# Mach_PCB.net
KiCad netlist of a schematic drawn in Altium Designer
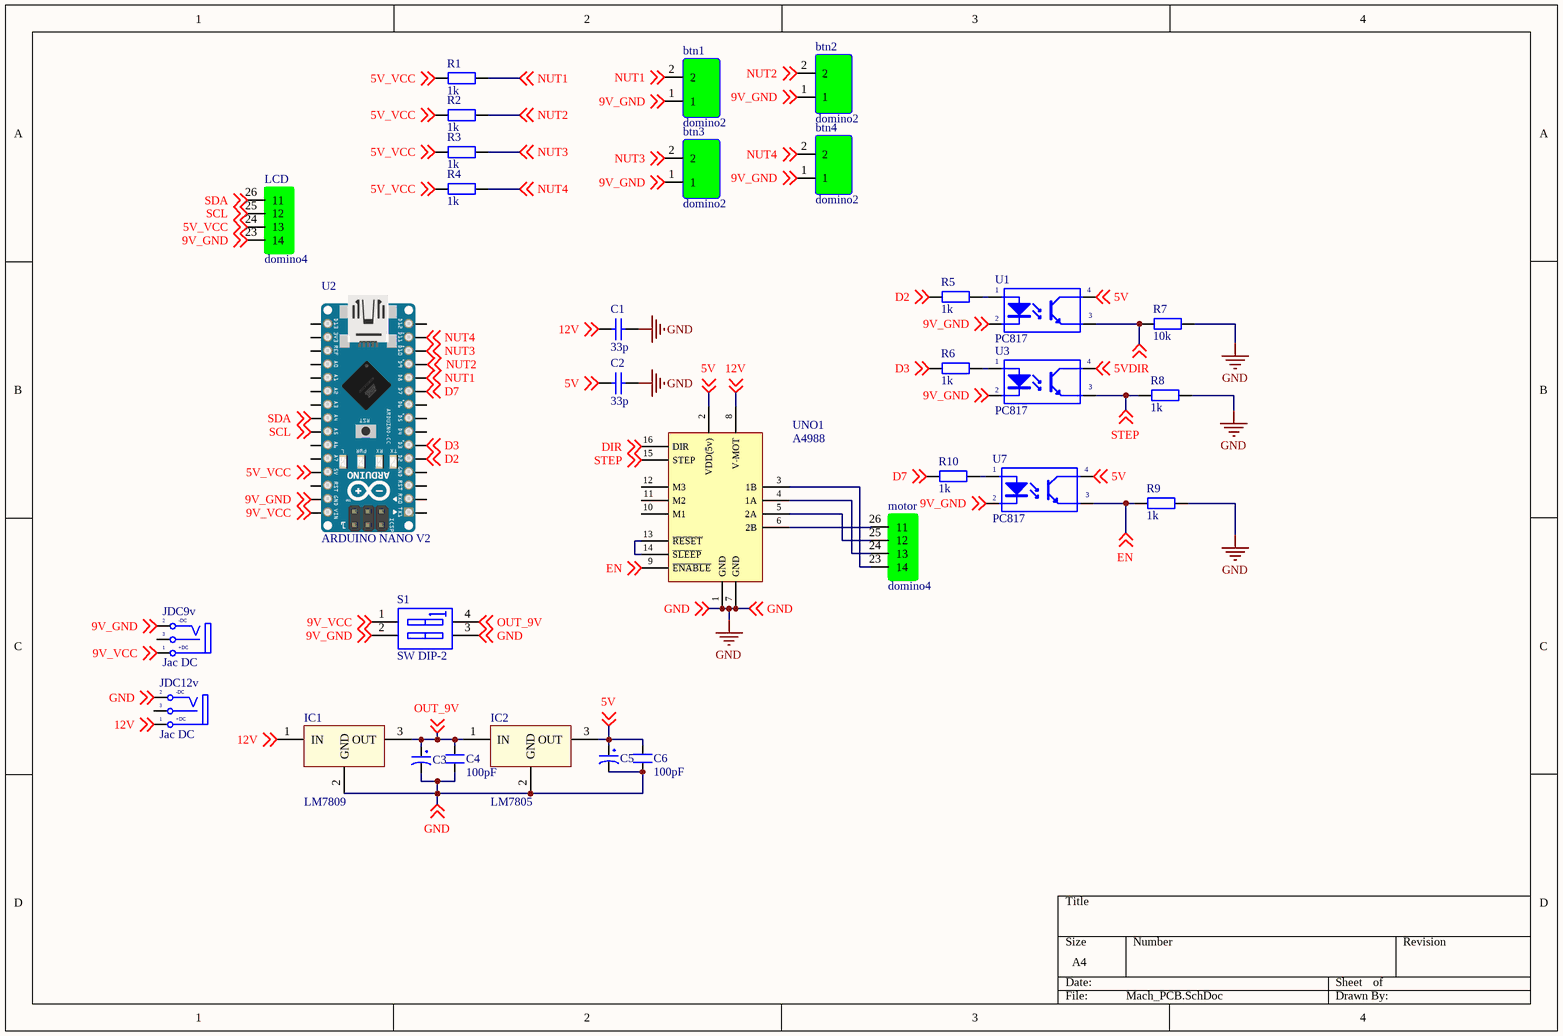
[diagram p0: Mach_PCB.SchDoc]

(export (version "E")
  (design (tool "Eeschema 10.0.6"))
  (components
    (comp (ref "btn1")
      (value "domino2")
      (footprint "domino2")
      (libsource (lib "Nanjar's Library") (part "domino2"))
    )
    (comp (ref "btn2")
      (value "domino2")
      (footprint "domino2")
      (libsource (lib "Nanjar's Library") (part "domino2"))
    )
    (comp (ref "btn3")
      (value "domino2")
      (footprint "domino2")
      (libsource (lib "Nanjar's Library") (part "domino2"))
    )
    (comp (ref "btn4")
      (value "domino2")
      (footprint "domino2")
      (libsource (lib "Nanjar's Library") (part "domino2"))
    )
    (comp (ref "C1")
      (value "33p")
      (footprint "Tu-ceramic")
      (description "Capacitor")
      (fields (field (name "Comment") "Capacitor Ceramic") (field (name "PUBLISHER") "Altium Limited"))
      (libsource (lib "NBBLib 14-03-2012") (part "CapDecop"))
    )
    (comp (ref "C2")
      (value "33p")
      (footprint "Tu-ceramic")
      (description "Capacitor")
      (fields (field (name "Comment") "Capacitor Ceramic") (field (name "PUBLISHER") "Altium Limited"))
      (libsource (lib "NBBLib 14-03-2012") (part "CapDecop"))
    )
    (comp (ref "C3")
      (value "100uF/35V")
      (footprint "CP1.5/3.4")
      (description "Cap 100uF/35V - 470uF/16V")
      (libsource (lib "Cty1") (part "CP3"))
    )
    (comp (ref "C4")
      (value "100pF")
      (footprint "CN1")
      (description "Cap np  1pF - 472pF")
      (libsource (lib "Cty1") (part "CN1"))
    )
    (comp (ref "C5")
      (value "100uF/35V")
      (footprint "CP1.5/3.4")
      (description "Cap 100uF/35V - 470uF/16V")
      (libsource (lib "Cty1") (part "CP3"))
    )
    (comp (ref "C6")
      (value "100pF")
      (footprint "CN1")
      (description "Cap np  1pF - 472pF")
      (libsource (lib "Cty1") (part "CN1"))
    )
    (comp (ref "IC1")
      (value "LM7809")
      (footprint "QTO-220")
      (description "On ap +, from + 5 to + 24VDC")
      (libsource (lib "Cty1") (part "LM78xx"))
    )
    (comp (ref "IC2")
      (value "LM7805")
      (footprint "QTO-220")
      (description "On ap +, from + 5 to + 24VDC")
      (libsource (lib "Cty1") (part "LM78xx"))
    )
    (comp (ref "JDC9v")
      (value "Jac DC")
      (footprint "DC-IN")
      (description "Jac DC input")
      (libsource (lib "Cty1") (part "DCIN"))
    )
    (comp (ref "JDC12v")
      (value "Jac DC")
      (footprint "DC-IN")
      (description "Jac DC input")
      (libsource (lib "Cty1") (part "DCIN"))
    )
    (comp (ref "LCD")
      (value "domino4")
      (footprint "domino4")
      (libsource (lib "Nanjar's Library") (part "domino4"))
    )
    (comp (ref "motor")
      (value "domino4")
      (footprint "domino4")
      (libsource (lib "Nanjar's Library") (part "domino4"))
    )
    (comp (ref "R1")
      (value "1k")
      (footprint "R1/4W")
      (description "Resistor 1/4W")
      (libsource (lib "Cty1") (part "R1/4W"))
    )
    (comp (ref "R2")
      (value "1k")
      (footprint "R1/4W")
      (description "Resistor 1/4W")
      (libsource (lib "Cty1") (part "R1/4W"))
    )
    (comp (ref "R3")
      (value "1k")
      (footprint "R1/4W")
      (description "Resistor 1/4W")
      (libsource (lib "Cty1") (part "R1/4W"))
    )
    (comp (ref "R4")
      (value "1k")
      (footprint "R1/4W")
      (description "Resistor 1/4W")
      (libsource (lib "Cty1") (part "R1/4W"))
    )
    (comp (ref "R5")
      (value "1k")
      (footprint "R1/4W")
      (description "Resistor 1/4W")
      (libsource (lib "Cty1") (part "R1/4W"))
    )
    (comp (ref "R6")
      (value "1k")
      (footprint "R1/4W")
      (description "Resistor 1/4W")
      (libsource (lib "Cty1") (part "R1/4W"))
    )
    (comp (ref "R7")
      (value "10k")
      (footprint "R1/4W")
      (description "Resistor 1/4W")
      (libsource (lib "Cty1") (part "R1/4W"))
    )
    (comp (ref "R8")
      (value "1k")
      (footprint "R1/4W")
      (description "Resistor 1/4W")
      (libsource (lib "Cty1") (part "R1/4W"))
    )
    (comp (ref "R9")
      (value "1k")
      (footprint "R1/4W")
      (description "Resistor 1/4W")
      (libsource (lib "Cty1") (part "R1/4W"))
    )
    (comp (ref "R10")
      (value "1k")
      (footprint "R1/4W")
      (description "Resistor 1/4W")
      (libsource (lib "Cty1") (part "R1/4W"))
    )
    (comp (ref "S1")
      (value "SW DIP-2")
      (footprint "DIP2")
      (description "DIP Switch, 2 Position, SPST")
      (fields (field (name "PUBLISHER") "Altium Limited"))
      (libsource (lib "My Library") (part "SW DIP-2"))
    )
    (comp (ref "U1")
      (value "PC817")
      (footprint "DIP4/W0.3")
      (description "Single Opto")
      (libsource (lib "syhaunguyen") (part "PC817"))
    )
    (comp (ref "U2")
      (value "ARDUINO NANO V2")
      (footprint "ARDUINO NANO")
      (libsource (lib "Nanjar's Library") (part "ARDUINO NANO V2"))
    )
    (comp (ref "U3")
      (value "PC817")
      (footprint "DIP4/W0.3")
      (description "Single Opto")
      (libsource (lib "syhaunguyen") (part "PC817"))
    )
    (comp (ref "U7")
      (value "PC817")
      (footprint "DIP4/W0.3")
      (description "Single Opto")
      (libsource (lib "syhaunguyen") (part "PC817"))
    )
    (comp (ref "UNO1")
      (value "A4988")
      (footprint "A4988(driver)")
      (libsource (lib "My Library") (part "A4988"))
    )
  )
  (nets
    (net (code "1") (name "5V") (class "Default")
      (node (ref "C2") (pin "2") (pinfunction "2_2") (pintype "passive"))
      (node (ref "C5") (pin "1") (pinfunction "1_1") (pintype "passive"))
      (node (ref "C6") (pin "1") (pinfunction "1_1") (pintype "passive"))
      (node (ref "IC2") (pin "3") (pinfunction "OUT_3") (pintype "passive"))
      (node (ref "U1") (pin "4") (pinfunction "C_4") (pintype "passive"))
      (node (ref "U3") (pin "4") (pinfunction "C_4") (pintype "passive"))
      (node (ref "U7") (pin "4") (pinfunction "C_4") (pintype "passive"))
      (node (ref "UNO1") (pin "2") (pinfunction "VDD(5v)_2") (pintype "power_in"))
    )
    (net (code "2") (name "5V_VCC") (class "Default")
      (node (ref "LCD") (pin "24") (pinfunction "13_24") (pintype "passive"))
      (node (ref "R1") (pin "1") (pinfunction "1_1") (pintype "passive"))
      (node (ref "R2") (pin "1") (pinfunction "1_1") (pintype "passive"))
      (node (ref "R3") (pin "1") (pinfunction "1_1") (pintype "passive"))
      (node (ref "R4") (pin "1") (pinfunction "1_1") (pintype "passive"))
      (node (ref "U2") (pin "27") (pinfunction "5V_27") (pintype "passive"))
    )
    (net (code "3") (name "9V_GND") (class "Default")
      (node (ref "JDC9v") (pin "2") (pinfunction "TN_2") (pintype "passive"))
      (node (ref "LCD") (pin "23") (pinfunction "14_23") (pintype "passive"))
      (node (ref "S1") (pin "2") (pinfunction "A2_2") (pintype "passive"))
      (node (ref "U1") (pin "2") (pinfunction "K_2") (pintype "passive"))
      (node (ref "U2") (pin "29") (pinfunction "GND_29") (pintype "passive"))
      (node (ref "U3") (pin "2") (pinfunction "K_2") (pintype "passive"))
      (node (ref "U7") (pin "2") (pinfunction "K_2") (pintype "passive"))
      (node (ref "btn1") (pin "1") (pinfunction "1_1") (pintype "passive"))
      (node (ref "btn2") (pin "1") (pinfunction "1_1") (pintype "passive"))
      (node (ref "btn3") (pin "1") (pinfunction "1_1") (pintype "passive"))
      (node (ref "btn4") (pin "1") (pinfunction "1_1") (pintype "passive"))
    )
    (net (code "4") (name "9V_VCC") (class "Default")
      (node (ref "JDC9v") (pin "1") (pinfunction "T_1") (pintype "passive"))
      (node (ref "S1") (pin "1") (pinfunction "A1_1") (pintype "passive"))
      (node (ref "U2") (pin "30") (pinfunction "VIN_30") (pintype "passive"))
    )
    (net (code "5") (name "12V") (class "Default")
      (node (ref "C1") (pin "2") (pinfunction "2_2") (pintype "passive"))
      (node (ref "IC1") (pin "1") (pinfunction "IN_1") (pintype "passive"))
      (node (ref "JDC12v") (pin "1") (pinfunction "T_1") (pintype "passive"))
      (node (ref "UNO1") (pin "8") (pinfunction "V-MOT_8") (pintype "power_in"))
    )
    (net (code "6") (name "D2") (class "Default")
      (node (ref "R5") (pin "1") (pinfunction "1_1") (pintype "passive"))
      (node (ref "U2") (pin "5") (pinfunction "D2_5") (pintype "passive"))
    )
    (net (code "7") (name "D3") (class "Default")
      (node (ref "R6") (pin "1") (pinfunction "1_1") (pintype "passive"))
      (node (ref "U2") (pin "6") (pinfunction "D3_6") (pintype "passive"))
    )
    (net (code "8") (name "D7") (class "Default")
      (node (ref "R10") (pin "1") (pinfunction "1_1") (pintype "passive"))
      (node (ref "U2") (pin "10") (pinfunction "D7_10") (pintype "passive"))
    )
    (net (code "9") (name "DIR") (class "Default")
      (node (ref "R7") (pin "1") (pinfunction "1_1") (pintype "passive"))
      (node (ref "U1") (pin "3") (pinfunction "E_3") (pintype "passive"))
      (node (ref "UNO1") (pin "16") (pinfunction "DIR_16") (pintype "power_in"))
    )
    (net (code "10") (name "EN") (class "Default")
      (node (ref "R9") (pin "1") (pinfunction "1_1") (pintype "passive"))
      (node (ref "U7") (pin "3") (pinfunction "E_3") (pintype "passive"))
      (node (ref "UNO1") (pin "9") (pinfunction "~{ENABLE}_9") (pintype "power_in"))
    )
    (net (code "11") (name "GND") (class "Default")
      (node (ref "C1") (pin "1") (pinfunction "1_1") (pintype "passive"))
      (node (ref "C2") (pin "1") (pinfunction "1_1") (pintype "passive"))
      (node (ref "C3") (pin "2") (pinfunction "2_2") (pintype "passive"))
      (node (ref "C4") (pin "2") (pinfunction "2_2") (pintype "passive"))
      (node (ref "C5") (pin "2") (pinfunction "2_2") (pintype "passive"))
      (node (ref "C6") (pin "2") (pinfunction "2_2") (pintype "passive"))
      (node (ref "IC1") (pin "2") (pinfunction "GND_2") (pintype "passive"))
      (node (ref "IC2") (pin "2") (pinfunction "GND_2") (pintype "passive"))
      (node (ref "JDC12v") (pin "2") (pinfunction "TN_2") (pintype "passive"))
      (node (ref "R7") (pin "2") (pinfunction "2_2") (pintype "passive"))
      (node (ref "R8") (pin "2") (pinfunction "2_2") (pintype "passive"))
      (node (ref "R9") (pin "2") (pinfunction "2_2") (pintype "passive"))
      (node (ref "S1") (pin "3") (pinfunction "B2_3") (pintype "passive"))
      (node (ref "UNO1") (pin "1") (pinfunction "GND_1") (pintype "power_in"))
      (node (ref "UNO1") (pin "7") (pinfunction "GND_7") (pintype "power_in"))
    )
    (net (code "12") (name "NUT1") (class "Default")
      (node (ref "R1") (pin "2") (pinfunction "2_2") (pintype "passive"))
      (node (ref "U2") (pin "11") (pinfunction "D8_11") (pintype "passive"))
      (node (ref "btn1") (pin "2") (pinfunction "2_2") (pintype "passive"))
    )
    (net (code "13") (name "NUT2") (class "Default")
      (node (ref "R2") (pin "2") (pinfunction "2_2") (pintype "passive"))
      (node (ref "btn2") (pin "2") (pinfunction "2_2") (pintype "passive"))
    )
    (net (code "14") (name "NUT3") (class "Default")
      (node (ref "R3") (pin "2") (pinfunction "2_2") (pintype "passive"))
      (node (ref "U2") (pin "13") (pinfunction "D10_13") (pintype "passive"))
      (node (ref "btn3") (pin "2") (pinfunction "2_2") (pintype "passive"))
    )
    (net (code "15") (name "NUT4") (class "Default")
      (node (ref "R4") (pin "2") (pinfunction "2_2") (pintype "passive"))
      (node (ref "U2") (pin "14") (pinfunction "D11_14") (pintype "passive"))
      (node (ref "btn4") (pin "2") (pinfunction "2_2") (pintype "passive"))
    )
    (net (code "16") (name "Net-(U1-A)") (class "Default")
      (node (ref "R5") (pin "2") (pinfunction "2_2") (pintype "passive"))
      (node (ref "U1") (pin "1") (pinfunction "A_1") (pintype "passive"))
    )
    (net (code "17") (name "Net-(U3-A)") (class "Default")
      (node (ref "R6") (pin "2") (pinfunction "2_2") (pintype "passive"))
      (node (ref "U3") (pin "1") (pinfunction "A_1") (pintype "passive"))
    )
    (net (code "18") (name "Net-(U7-A)") (class "Default")
      (node (ref "R10") (pin "2") (pinfunction "2_2") (pintype "passive"))
      (node (ref "U7") (pin "1") (pinfunction "A_1") (pintype "passive"))
    )
    (net (code "19") (name "Net-(UNO1-1A)") (class "Default")
      (node (ref "UNO1") (pin "4") (pinfunction "1A_4") (pintype "power_in"))
      (node (ref "motor") (pin "24") (pinfunction "13_24") (pintype "passive"))
    )
    (net (code "20") (name "Net-(UNO1-1B)") (class "Default")
      (node (ref "UNO1") (pin "3") (pinfunction "1B_3") (pintype "power_in"))
      (node (ref "motor") (pin "23") (pinfunction "14_23") (pintype "passive"))
    )
    (net (code "21") (name "Net-(UNO1-2A)") (class "Default")
      (node (ref "UNO1") (pin "5") (pinfunction "2A_5") (pintype "power_in"))
      (node (ref "motor") (pin "25") (pinfunction "12_25") (pintype "passive"))
    )
    (net (code "22") (name "Net-(UNO1-2B)") (class "Default")
      (node (ref "UNO1") (pin "6") (pinfunction "2B_6") (pintype "power_in"))
      (node (ref "motor") (pin "26") (pinfunction "11_26") (pintype "passive"))
    )
    (net (code "23") (name "Net-(UNO1-~{RESET})") (class "Default")
      (node (ref "UNO1") (pin "13") (pinfunction "~{RESET}_13") (pintype "power_in"))
      (node (ref "UNO1") (pin "14") (pinfunction "~{SLEEP}_14") (pintype "power_in"))
    )
    (net (code "24") (name "OUT_9V") (class "Default")
      (node (ref "C3") (pin "1") (pinfunction "1_1") (pintype "passive"))
      (node (ref "C4") (pin "1") (pinfunction "1_1") (pintype "passive"))
      (node (ref "IC1") (pin "3") (pinfunction "OUT_3") (pintype "passive"))
      (node (ref "IC2") (pin "1") (pinfunction "IN_1") (pintype "passive"))
      (node (ref "S1") (pin "4") (pinfunction "B1_4") (pintype "passive"))
    )
    (net (code "25") (name "SCL") (class "Default")
      (node (ref "LCD") (pin "25") (pinfunction "12_25") (pintype "passive"))
      (node (ref "U2") (pin "24") (pinfunction "A5_24") (pintype "passive"))
    )
    (net (code "26") (name "SDA") (class "Default")
      (node (ref "LCD") (pin "26") (pinfunction "11_26") (pintype "passive"))
      (node (ref "U2") (pin "23") (pinfunction "A4_23") (pintype "passive"))
    )
    (net (code "27") (name "STEP") (class "Default")
      (node (ref "R8") (pin "1") (pinfunction "1_1") (pintype "passive"))
      (node (ref "U3") (pin "3") (pinfunction "E_3") (pintype "passive"))
      (node (ref "UNO1") (pin "15") (pinfunction "STEP_15") (pintype "power_in"))
    )
    (net (code "28") (name "unconnected-(JDC9v-S-Pad3)") (class "Default")
      (node (ref "JDC9v") (pin "3") (pinfunction "S_3") (pintype "power_in"))
    )
    (net (code "29") (name "unconnected-(JDC12v-S-Pad3)") (class "Default")
      (node (ref "JDC12v") (pin "3") (pinfunction "S_3") (pintype "power_in"))
    )
    (net (code "30") (name "unconnected-(U2-3-PadRST)") (class "Default")
      (node (ref "U2") (pin "RST") (pinfunction "3_RST") (pintype "passive"))
    )
    (net (code "31") (name "unconnected-(U2-3V3-Pad17)") (class "Default")
      (node (ref "U2") (pin "17") (pinfunction "3V3_17") (pintype "passive"))
    )
    (net (code "32") (name "unconnected-(U2-A0-Pad19)") (class "Default")
      (node (ref "U2") (pin "19") (pinfunction "A0_19") (pintype "passive"))
    )
    (net (code "33") (name "unconnected-(U2-A1-Pad20)") (class "Default")
      (node (ref "U2") (pin "20") (pinfunction "A1_20") (pintype "passive"))
    )
    (net (code "34") (name "unconnected-(U2-A2-Pad21)") (class "Default")
      (node (ref "U2") (pin "21") (pinfunction "A2_21") (pintype "passive"))
    )
    (net (code "35") (name "unconnected-(U2-A3-Pad22)") (class "Default")
      (node (ref "U2") (pin "22") (pinfunction "A3_22") (pintype "passive"))
    )
    (net (code "36") (name "unconnected-(U2-A6-Pad25)") (class "Default")
      (node (ref "U2") (pin "25") (pinfunction "A6_25") (pintype "passive"))
    )
    (net (code "37") (name "unconnected-(U2-A7-Pad26)") (class "Default")
      (node (ref "U2") (pin "26") (pinfunction "A7_26") (pintype "passive"))
    )
    (net (code "38") (name "unconnected-(U2-AREF-Pad18)") (class "Default")
      (node (ref "U2") (pin "18") (pinfunction "AREF_18") (pintype "passive"))
    )
    (net (code "39") (name "unconnected-(U2-D4-Pad7)") (class "Default")
      (node (ref "U2") (pin "7") (pinfunction "D4_7") (pintype "passive"))
    )
    (net (code "40") (name "unconnected-(U2-D5-Pad8)") (class "Default")
      (node (ref "U2") (pin "8") (pinfunction "D5_8") (pintype "passive"))
    )
    (net (code "41") (name "unconnected-(U2-D6-Pad9)") (class "Default")
      (node (ref "U2") (pin "9") (pinfunction "D6_9") (pintype "passive"))
    )
    (net (code "42") (name "unconnected-(U2-D9-Pad12)") (class "Default")
      (node (ref "U2") (pin "12") (pinfunction "D9_12") (pintype "passive"))
    )
    (net (code "43") (name "unconnected-(U2-D12-Pad15)") (class "Default")
      (node (ref "U2") (pin "15") (pinfunction "D12_15") (pintype "passive"))
    )
    (net (code "44") (name "unconnected-(U2-D13-Pad16)") (class "Default")
      (node (ref "U2") (pin "16") (pinfunction "D13_16") (pintype "passive"))
    )
    (net (code "45") (name "unconnected-(U2-GND-Pad4)") (class "Default")
      (node (ref "U2") (pin "4") (pinfunction "GND_4") (pintype "passive"))
    )
    (net (code "46") (name "unconnected-(U2-RST-Pad28)") (class "Default")
      (node (ref "U2") (pin "28") (pinfunction "RST_28") (pintype "passive"))
    )
    (net (code "47") (name "unconnected-(U2-RX-Pad2)") (class "Default")
      (node (ref "U2") (pin "2") (pinfunction "RX_2") (pintype "passive"))
    )
    (net (code "48") (name "unconnected-(U2-TX-Pad1)") (class "Default")
      (node (ref "U2") (pin "1") (pinfunction "TX_1") (pintype "passive"))
    )
    (net (code "49") (name "unconnected-(UNO1-M1-Pad10)") (class "Default")
      (node (ref "UNO1") (pin "10") (pinfunction "M1_10") (pintype "power_in"))
    )
    (net (code "50") (name "unconnected-(UNO1-M2-Pad11)") (class "Default")
      (node (ref "UNO1") (pin "11") (pinfunction "M2_11") (pintype "power_in"))
    )
    (net (code "51") (name "unconnected-(UNO1-M3-Pad12)") (class "Default")
      (node (ref "UNO1") (pin "12") (pinfunction "M3_12") (pintype "power_in"))
    )
  )
)
